# STM32.net
KiCad netlist of a schematic drawn in Altium Designer
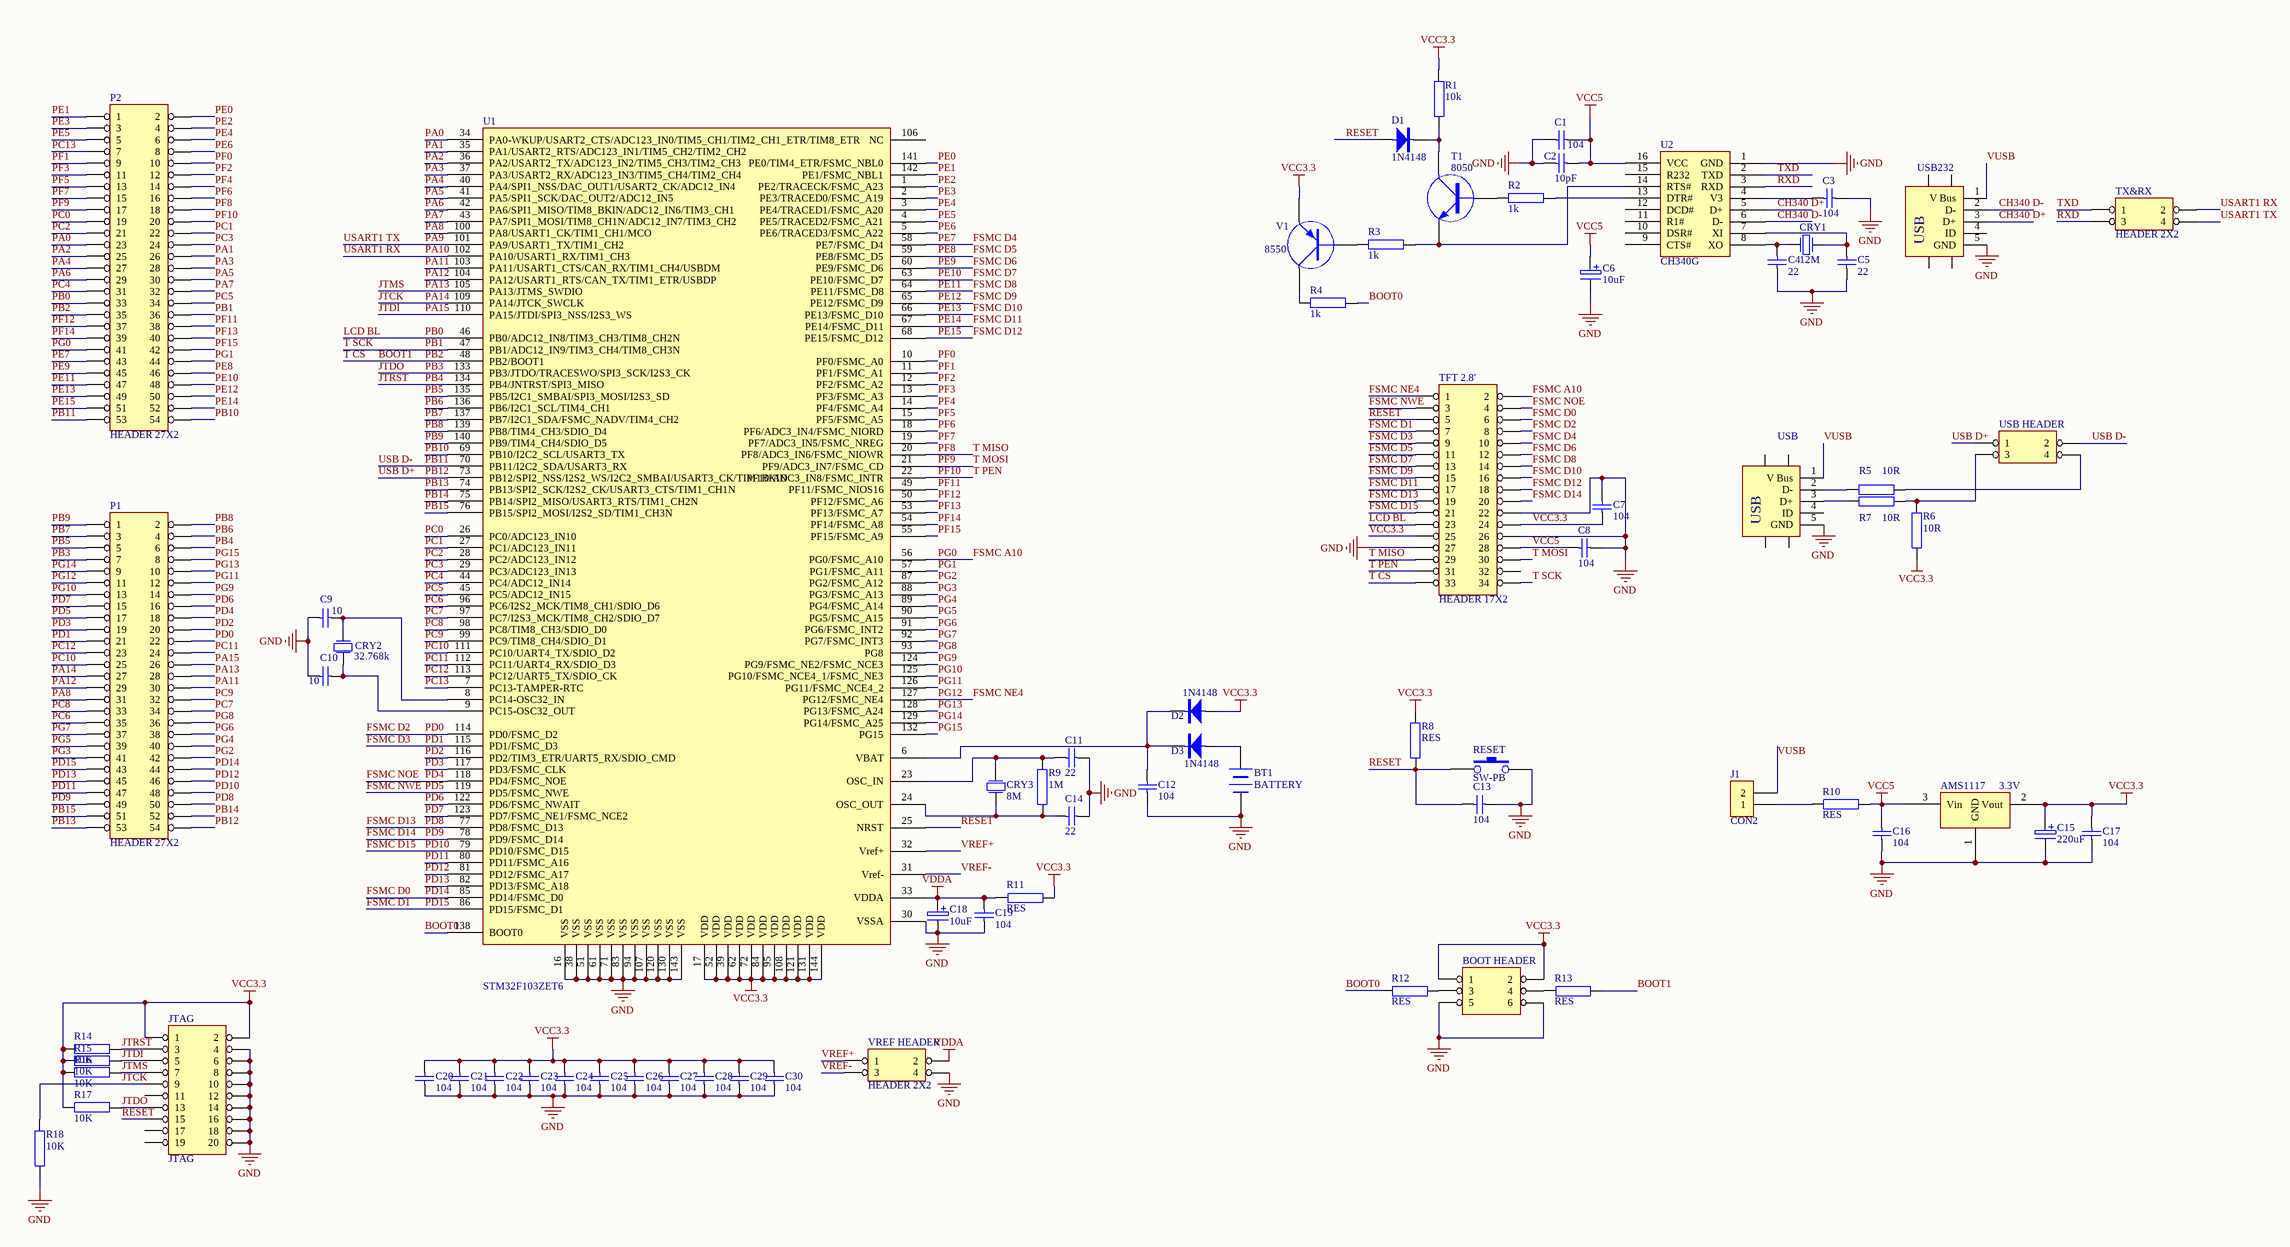
[diagram p0: STM32最小系统.SchDoc]

(export (version "E")
  (design (tool "Eeschema 10.0.6"))
  (components
    (comp (ref "AMS1117") (value "3.3V") (footprint "SOT-223") (libsource (lib "刘杨_元件库") (part "LD1117")))
    (comp (ref "BOOT HEADER")
      (value "HEADER 3X2")
      (footprint "3X2DIP")
      (libsource (lib "接口") (part "HEADER 3X2"))
    )
    (comp (ref "BT1")
      (value "BATTERY")
      (footprint "POWER1")
      (description "Battery")
      (libsource (lib "Other其它") (part "BATTERY"))
    )
    (comp (ref "C1")
      (value "104")
      (footprint "C0805")
      (description "Capacitor")
      (fields (field (name "PUBLISHER") "Altium Limited"))
      (libsource (lib "Capacitance电容") (part "Cap"))
    )
    (comp (ref "C2")
      (value "10pF")
      (footprint "C0805")
      (description "Capacitor")
      (fields (field (name "PUBLISHER") "Altium Limited"))
      (libsource (lib "Capacitance电容") (part "Cap"))
    )
    (comp (ref "C3")
      (value "104")
      (footprint "C0805")
      (description "Capacitor")
      (fields (field (name "PUBLISHER") "Altium Limited"))
      (libsource (lib "Capacitance电容") (part "Cap"))
    )
    (comp (ref "C4")
      (value "22")
      (footprint "C0805")
      (description "Capacitor")
      (fields (field (name "PUBLISHER") "Altium Limited"))
      (libsource (lib "Capacitance电容") (part "Cap"))
    )
    (comp (ref "C5")
      (value "22")
      (footprint "C0805")
      (description "Capacitor")
      (fields (field (name "PUBLISHER") "Altium Limited"))
      (libsource (lib "Capacitance电容") (part "Cap"))
    )
    (comp (ref "C6") (value "10uF") (footprint "CAO1") (libsource (lib "C电容") (part "CAP3")))
    (comp (ref "C7")
      (value "104")
      (footprint "C0805")
      (description "Capacitor")
      (fields (field (name "PUBLISHER") "Altium Limited"))
      (libsource (lib "Capacitance电容") (part "Cap"))
    )
    (comp (ref "C8")
      (value "104")
      (footprint "C0805")
      (description "Capacitor")
      (fields (field (name "PUBLISHER") "Altium Limited"))
      (libsource (lib "Capacitance电容") (part "Cap"))
    )
    (comp (ref "C9")
      (value "10")
      (footprint "C0805")
      (description "Capacitor")
      (fields (field (name "PUBLISHER") "Altium Limited"))
      (libsource (lib "Capacitance电容") (part "Cap"))
    )
    (comp (ref "C10")
      (value "10")
      (footprint "C0805")
      (description "Capacitor")
      (fields (field (name "PUBLISHER") "Altium Limited"))
      (libsource (lib "Capacitance电容") (part "Cap"))
    )
    (comp (ref "C11")
      (value "22")
      (footprint "C0805")
      (description "Capacitor")
      (fields (field (name "PUBLISHER") "Altium Limited"))
      (libsource (lib "Capacitance电容") (part "Cap"))
    )
    (comp (ref "C12")
      (value "104")
      (footprint "C0805")
      (description "Capacitor")
      (fields (field (name "PUBLISHER") "Altium Limited"))
      (libsource (lib "Capacitance电容") (part "Cap"))
    )
    (comp (ref "C13")
      (value "104")
      (footprint "C0805")
      (description "Capacitor")
      (fields (field (name "PUBLISHER") "Altium Limited"))
      (libsource (lib "Capacitance电容") (part "Cap"))
    )
    (comp (ref "C14")
      (value "22")
      (footprint "C0805")
      (description "Capacitor")
      (fields (field (name "PUBLISHER") "Altium Limited"))
      (libsource (lib "Capacitance电容") (part "Cap"))
    )
    (comp (ref "C15") (value "220uF") (footprint "CAO1") (libsource (lib "C电容") (part "CAP3")))
    (comp (ref "C16")
      (value "104")
      (footprint "C0805")
      (description "Capacitor")
      (fields (field (name "PUBLISHER") "Altium Limited"))
      (libsource (lib "Capacitance电容") (part "Cap"))
    )
    (comp (ref "C17")
      (value "104")
      (footprint "C0805")
      (description "Capacitor")
      (fields (field (name "PUBLISHER") "Altium Limited"))
      (libsource (lib "Capacitance电容") (part "Cap"))
    )
    (comp (ref "C18") (value "10uF") (footprint "CAO1") (libsource (lib "C电容") (part "CAP3")))
    (comp (ref "C19")
      (value "104")
      (footprint "C0805")
      (description "Capacitor")
      (fields (field (name "PUBLISHER") "Altium Limited"))
      (libsource (lib "Capacitance电容") (part "Cap"))
    )
    (comp (ref "C20")
      (value "104")
      (footprint "C0805")
      (description "Capacitor")
      (fields (field (name "PUBLISHER") "Altium Limited"))
      (libsource (lib "Capacitance电容") (part "Cap"))
    )
    (comp (ref "C21")
      (value "104")
      (footprint "C0805")
      (description "Capacitor")
      (fields (field (name "PUBLISHER") "Altium Limited"))
      (libsource (lib "Capacitance电容") (part "Cap"))
    )
    (comp (ref "C22")
      (value "104")
      (footprint "C0805")
      (description "Capacitor")
      (fields (field (name "PUBLISHER") "Altium Limited"))
      (libsource (lib "Capacitance电容") (part "Cap"))
    )
    (comp (ref "C23")
      (value "104")
      (footprint "C0805")
      (description "Capacitor")
      (fields (field (name "PUBLISHER") "Altium Limited"))
      (libsource (lib "Capacitance电容") (part "Cap"))
    )
    (comp (ref "C24")
      (value "104")
      (footprint "C0805")
      (description "Capacitor")
      (fields (field (name "PUBLISHER") "Altium Limited"))
      (libsource (lib "Capacitance电容") (part "Cap"))
    )
    (comp (ref "C25")
      (value "104")
      (footprint "C0805")
      (description "Capacitor")
      (fields (field (name "PUBLISHER") "Altium Limited"))
      (libsource (lib "Capacitance电容") (part "Cap"))
    )
    (comp (ref "C26")
      (value "104")
      (footprint "C0805")
      (description "Capacitor")
      (fields (field (name "PUBLISHER") "Altium Limited"))
      (libsource (lib "Capacitance电容") (part "Cap"))
    )
    (comp (ref "C27")
      (value "104")
      (footprint "C0805")
      (description "Capacitor")
      (fields (field (name "PUBLISHER") "Altium Limited"))
      (libsource (lib "Capacitance电容") (part "Cap"))
    )
    (comp (ref "C28")
      (value "104")
      (footprint "C0805")
      (description "Capacitor")
      (fields (field (name "PUBLISHER") "Altium Limited"))
      (libsource (lib "Capacitance电容") (part "Cap"))
    )
    (comp (ref "C29")
      (value "104")
      (footprint "C0805")
      (description "Capacitor")
      (fields (field (name "PUBLISHER") "Altium Limited"))
      (libsource (lib "Capacitance电容") (part "Cap"))
    )
    (comp (ref "C30")
      (value "104")
      (footprint "C0805")
      (description "Capacitor")
      (fields (field (name "PUBLISHER") "Altium Limited"))
      (libsource (lib "Capacitance电容") (part "Cap"))
    )
    (comp (ref "CRY1")
      (value "12M")
      (footprint "JZ1")
      (description "6.0000 8.000  11.0592  12.0000 24.000")
      (libsource (lib "J晶振") (part "CRY1"))
    )
    (comp (ref "CRY2")
      (value "32.768k")
      (footprint "JZ_O1")
      (description "6.0000 8.000  11.0592  12.0000 24.000")
      (libsource (lib "J晶振") (part "CRY1"))
    )
    (comp (ref "CRY3")
      (value "8M")
      (footprint "JZ1")
      (description "6.0000 8.000  11.0592  12.0000 24.000")
      (libsource (lib "J晶振") (part "CRY1"))
    )
    (comp (ref "D1") (value "1N4148") (footprint "DIODE0.4") (libsource (lib "") (part "DIODE_1")))
    (comp (ref "D2") (value "1N4148") (footprint "DIODE0.4") (libsource (lib "Diode二极管") (part "DIODE")))
    (comp (ref "D3") (value "1N4148") (footprint "DIODE0.4") (libsource (lib "Diode二极管") (part "DIODE")))
    (comp (ref "J1")
      (value "CON2")
      (footprint "sip-2")
      (description "Connector")
      (libsource (lib "接口") (part "CON2"))
    )
    (comp (ref "JTAG") (value "JTAG") (footprint "10x2DIP") (libsource (lib "接口") (part "HEADER 10X2")))
    (comp (ref "P1")
      (value "HEADER 27X2")
      (footprint "27X2DIP")
      (libsource (lib "Plugs插头") (part "HEADER 27X2"))
    )
    (comp (ref "P2")
      (value "HEADER 27X2")
      (footprint "27X2DIP")
      (libsource (lib "Plugs插头") (part "HEADER 27X2"))
    )
    (comp (ref "R1") (value "10k") (footprint "R0805") (libsource (lib "R电阻") (part "RES")))
    (comp (ref "R2") (value "1k") (footprint "R0805") (libsource (lib "R电阻") (part "RES")))
    (comp (ref "R3") (value "1k") (footprint "R0805") (libsource (lib "R电阻") (part "RES")))
    (comp (ref "R4") (value "1k") (footprint "R0805") (libsource (lib "R电阻") (part "RES")))
    (comp (ref "R5") (value "10R") (footprint "R0805") (libsource (lib "R电阻") (part "RES")))
    (comp (ref "R6") (value "10R") (footprint "R0805") (libsource (lib "R电阻") (part "RES")))
    (comp (ref "R7") (value "10R") (footprint "R0805") (libsource (lib "R电阻") (part "RES")))
    (comp (ref "R8") (value "RES") (footprint "R0805") (libsource (lib "R电阻") (part "RES")))
    (comp (ref "R9") (value "1M") (footprint "R0805") (libsource (lib "R电阻") (part "RES")))
    (comp (ref "R10") (value "RES") (footprint "R0805") (libsource (lib "R电阻") (part "RES")))
    (comp (ref "R11") (value "RES") (footprint "R0805") (libsource (lib "R电阻") (part "RES")))
    (comp (ref "R12") (value "RES") (footprint "R0805") (libsource (lib "R电阻") (part "RES")))
    (comp (ref "R13") (value "RES") (footprint "R0805") (libsource (lib "R电阻") (part "RES")))
    (comp (ref "R14") (value "10K") (footprint "R0805") (libsource (lib "R电阻") (part "RES")))
    (comp (ref "R15") (value "10K") (footprint "R0805") (libsource (lib "R电阻") (part "RES")))
    (comp (ref "R16") (value "10K") (footprint "R0805") (libsource (lib "R电阻") (part "RES")))
    (comp (ref "R17") (value "10K") (footprint "R0805") (libsource (lib "R电阻") (part "RES")))
    (comp (ref "R18") (value "10K") (footprint "R0805") (libsource (lib "R电阻") (part "RES")))
    (comp (ref "RESET") (value "SW-PB") (footprint "按键 15mm*15mm") (libsource (lib "SW开关") (part "SW-PB")))
    (comp (ref "T1") (value "8050") (footprint "TO-92") (libsource (lib "V三极管") (part "8050")))
    (comp (ref "TFT 2.8'")
      (value "HEADER 17X2")
      (footprint "17X2DIP")
      (libsource (lib "Plugs插头") (part "HEADER 17X2"))
    )
    (comp (ref "TX&RX") (value "HEADER 2X2") (footprint "2X2DIP") (libsource (lib "接口") (part "HEADER 2X2")))
    (comp (ref "U1")
      (value "STM32F103ZET6")
      (footprint "LQFN144")
      (libsource (lib "STM32") (part "STM32F103ZET6"))
    )
    (comp (ref "U2") (value "CH340G") (footprint "SOP16") (libsource (lib "ORDER其它") (part "CH340G")))
    (comp (ref "USB") (value "~") (footprint "USB_mini_B") (libsource (lib "Plugs插头") (part "USB_mini_B")))
    (comp (ref "USB HEADER") (value "~") (footprint "2X2DIP") (libsource (lib "接口") (part "HEADER 2X2")))
    (comp (ref "USB232") (value "~") (footprint "USB_mini_B") (libsource (lib "Plugs插头") (part "USB_mini_B")))
    (comp (ref "V1") (value "8550") (footprint "TO-92") (libsource (lib "V三极管") (part "8550")))
    (comp (ref "VREF HEADER")
      (value "HEADER 2X2")
      (footprint "2X2DIP")
      (libsource (lib "接口") (part "HEADER 2X2"))
    )
  )
  (nets
    (net (code "1") (name "/BOOT0") (class "Default")
      (node (ref "R12") (pin "1") (pinfunction "1_1") (pintype "passive"))
      (node (ref "R4") (pin "1") (pinfunction "1_1") (pintype "passive"))
      (node (ref "U1") (pin "138") (pinfunction "BOOT0_138") (pintype "passive"))
    )
    (net (code "2") (name "/BOOT1") (class "Default")
      (node (ref "P2") (pin "35") (pinfunction "35_35") (pintype "passive"))
      (node (ref "R13") (pin "2") (pinfunction "2_2") (pintype "passive"))
      (node (ref "TFT 2.8'") (pin "33") (pinfunction "33_33") (pintype "passive"))
      (node (ref "U1") (pin "48") (pinfunction "PB2/BOOT1_48") (pintype "passive"))
    )
    (net (code "3") (name "/CH340 D+") (class "Default")
      (node (ref "U2") (pin "5") (pinfunction "D+_5") (pintype "passive"))
      (node (ref "USB232") (pin "3") (pinfunction "D+_3") (pintype "passive"))
    )
    (net (code "4") (name "/CH340 D-") (class "Default")
      (node (ref "U2") (pin "6") (pinfunction "D-_6") (pintype "passive"))
      (node (ref "USB232") (pin "2") (pinfunction "D-_2") (pintype "passive"))
    )
    (net (code "5") (name "/FSMC A10") (class "Default")
      (node (ref "P2") (pin "41") (pinfunction "41_41") (pintype "passive"))
      (node (ref "TFT 2.8'") (pin "2") (pinfunction "2_2") (pintype "passive"))
      (node (ref "U1") (pin "56") (pinfunction "PG0/FSMC_A10_56") (pintype "passive"))
    )
    (net (code "6") (name "/FSMC D0") (class "Default")
      (node (ref "P1") (pin "44") (pinfunction "44_44") (pintype "passive"))
      (node (ref "TFT 2.8'") (pin "6") (pinfunction "6_6") (pintype "passive"))
      (node (ref "U1") (pin "85") (pinfunction "PD14/FSMC_D0_85") (pintype "passive"))
    )
    (net (code "7") (name "/FSMC D1") (class "Default")
      (node (ref "P1") (pin "43") (pinfunction "43_43") (pintype "passive"))
      (node (ref "TFT 2.8'") (pin "7") (pinfunction "7_7") (pintype "passive"))
      (node (ref "U1") (pin "86") (pinfunction "PD15/FSMC_D1_86") (pintype "passive"))
    )
    (net (code "8") (name "/FSMC D2") (class "Default")
      (node (ref "P1") (pin "22") (pinfunction "22_22") (pintype "passive"))
      (node (ref "TFT 2.8'") (pin "8") (pinfunction "8_8") (pintype "passive"))
      (node (ref "U1") (pin "114") (pinfunction "PD0/FSMC_D2_114") (pintype "passive"))
    )
    (net (code "9") (name "/FSMC D3") (class "Default")
      (node (ref "P1") (pin "21") (pinfunction "21_21") (pintype "passive"))
      (node (ref "TFT 2.8'") (pin "9") (pinfunction "9_9") (pintype "passive"))
      (node (ref "U1") (pin "115") (pinfunction "PD1/FSMC_D3_115") (pintype "passive"))
    )
    (net (code "10") (name "/FSMC D4") (class "Default")
      (node (ref "P2") (pin "43") (pinfunction "43_43") (pintype "passive"))
      (node (ref "TFT 2.8'") (pin "10") (pinfunction "10_10") (pintype "passive"))
      (node (ref "U1") (pin "58") (pinfunction "PE7/FSMC_D4_58") (pintype "passive"))
    )
    (net (code "11") (name "/FSMC D5") (class "Default")
      (node (ref "P2") (pin "46") (pinfunction "46_46") (pintype "passive"))
      (node (ref "TFT 2.8'") (pin "11") (pinfunction "11_11") (pintype "passive"))
      (node (ref "U1") (pin "59") (pinfunction "PE8/FSMC_D5_59") (pintype "passive"))
    )
    (net (code "12") (name "/FSMC D6") (class "Default")
      (node (ref "P2") (pin "45") (pinfunction "45_45") (pintype "passive"))
      (node (ref "TFT 2.8'") (pin "12") (pinfunction "12_12") (pintype "passive"))
      (node (ref "U1") (pin "60") (pinfunction "PE9/FSMC_D6_60") (pintype "passive"))
    )
    (net (code "13") (name "/FSMC D7") (class "Default")
      (node (ref "P2") (pin "48") (pinfunction "48_48") (pintype "passive"))
      (node (ref "TFT 2.8'") (pin "13") (pinfunction "13_13") (pintype "passive"))
      (node (ref "U1") (pin "63") (pinfunction "PE10/FSMC_D7_63") (pintype "passive"))
    )
    (net (code "14") (name "/FSMC D8") (class "Default")
      (node (ref "P2") (pin "47") (pinfunction "47_47") (pintype "passive"))
      (node (ref "TFT 2.8'") (pin "14") (pinfunction "14_14") (pintype "passive"))
      (node (ref "U1") (pin "64") (pinfunction "PE11/FSMC_D8_64") (pintype "passive"))
    )
    (net (code "15") (name "/FSMC D9") (class "Default")
      (node (ref "P2") (pin "50") (pinfunction "50_50") (pintype "passive"))
      (node (ref "TFT 2.8'") (pin "15") (pinfunction "15_15") (pintype "passive"))
      (node (ref "U1") (pin "65") (pinfunction "PE12/FSMC_D9_65") (pintype "passive"))
    )
    (net (code "16") (name "/FSMC D10") (class "Default")
      (node (ref "P2") (pin "49") (pinfunction "49_49") (pintype "passive"))
      (node (ref "TFT 2.8'") (pin "16") (pinfunction "16_16") (pintype "passive"))
      (node (ref "U1") (pin "66") (pinfunction "PE13/FSMC_D10_66") (pintype "passive"))
    )
    (net (code "17") (name "/FSMC D11") (class "Default")
      (node (ref "P2") (pin "52") (pinfunction "52_52") (pintype "passive"))
      (node (ref "TFT 2.8'") (pin "17") (pinfunction "17_17") (pintype "passive"))
      (node (ref "U1") (pin "67") (pinfunction "PE14/FSMC_D11_67") (pintype "passive"))
    )
    (net (code "18") (name "/FSMC D12") (class "Default")
      (node (ref "P2") (pin "51") (pinfunction "51_51") (pintype "passive"))
      (node (ref "TFT 2.8'") (pin "18") (pinfunction "18_18") (pintype "passive"))
      (node (ref "U1") (pin "68") (pinfunction "PE15/FSMC_D12_68") (pintype "passive"))
    )
    (net (code "19") (name "/FSMC D13") (class "Default")
      (node (ref "P1") (pin "50") (pinfunction "50_50") (pintype "passive"))
      (node (ref "TFT 2.8'") (pin "19") (pinfunction "19_19") (pintype "passive"))
      (node (ref "U1") (pin "77") (pinfunction "PD8/FSMC_D13_77") (pintype "passive"))
    )
    (net (code "20") (name "/FSMC D14") (class "Default")
      (node (ref "P1") (pin "49") (pinfunction "49_49") (pintype "passive"))
      (node (ref "TFT 2.8'") (pin "20") (pinfunction "20_20") (pintype "passive"))
      (node (ref "U1") (pin "78") (pinfunction "PD9/FSMC_D14_78") (pintype "passive"))
    )
    (net (code "21") (name "/FSMC D15") (class "Default")
      (node (ref "P1") (pin "48") (pinfunction "48_48") (pintype "passive"))
      (node (ref "TFT 2.8'") (pin "21") (pinfunction "21_21") (pintype "passive"))
      (node (ref "U1") (pin "79") (pinfunction "PD10/FSMC_D15_79") (pintype "passive"))
    )
    (net (code "22") (name "/FSMC NE4") (class "Default")
      (node (ref "P1") (pin "11") (pinfunction "11_11") (pintype "passive"))
      (node (ref "TFT 2.8'") (pin "1") (pinfunction "1_1") (pintype "passive"))
      (node (ref "U1") (pin "127") (pinfunction "PG12/FSMC_NE4_127") (pintype "passive"))
    )
    (net (code "23") (name "/FSMC NOE") (class "Default")
      (node (ref "P1") (pin "18") (pinfunction "18_18") (pintype "passive"))
      (node (ref "TFT 2.8'") (pin "4") (pinfunction "4_4") (pintype "passive"))
      (node (ref "U1") (pin "118") (pinfunction "PD4/FSMC_NOE_118") (pintype "passive"))
    )
    (net (code "24") (name "/FSMC NWE") (class "Default")
      (node (ref "P1") (pin "17") (pinfunction "17_17") (pintype "passive"))
      (node (ref "TFT 2.8'") (pin "3") (pinfunction "3_3") (pintype "passive"))
      (node (ref "U1") (pin "119") (pinfunction "PD5/FSMC_NWE_119") (pintype "passive"))
    )
    (net (code "25") (name "/JTCK") (class "Default")
      (node (ref "JTAG") (pin "9") (pinfunction "9_9") (pintype "passive"))
      (node (ref "P1") (pin "27") (pinfunction "27_27") (pintype "passive"))
      (node (ref "R18") (pin "2") (pinfunction "2_2") (pintype "passive"))
      (node (ref "U1") (pin "109") (pinfunction "PA14/JTCK_SWCLK_109") (pintype "passive"))
    )
    (net (code "26") (name "/JTDI") (class "Default")
      (node (ref "JTAG") (pin "5") (pinfunction "5_5") (pintype "passive"))
      (node (ref "P1") (pin "26") (pinfunction "26_26") (pintype "passive"))
      (node (ref "R15") (pin "1") (pinfunction "1_1") (pintype "passive"))
      (node (ref "U1") (pin "110") (pinfunction "PA15/JTDI/SPI3_NSS/I2S3_WS_110") (pintype "passive"))
    )
    (net (code "27") (name "/JTDO") (class "Default")
      (node (ref "JTAG") (pin "13") (pinfunction "13_13") (pintype "passive"))
      (node (ref "P1") (pin "7") (pinfunction "7_7") (pintype "passive"))
      (node (ref "R17") (pin "1") (pinfunction "1_1") (pintype "passive"))
      (node (ref "U1") (pin "133") (pinfunction "PB3/JTDO/TRACESWO/SPI3_SCK/I2S3_CK_133") (pintype "passive"))
    )
    (net (code "28") (name "/JTMS") (class "Default")
      (node (ref "JTAG") (pin "7") (pinfunction "7_7") (pintype "passive"))
      (node (ref "P1") (pin "28") (pinfunction "28_28") (pintype "passive"))
      (node (ref "R16") (pin "1") (pinfunction "1_1") (pintype "passive"))
      (node (ref "U1") (pin "105") (pinfunction "PA13/JTMS_SWDIO_105") (pintype "passive"))
    )
    (net (code "29") (name "/JTRST") (class "Default")
      (node (ref "JTAG") (pin "3") (pinfunction "3_3") (pintype "passive"))
      (node (ref "P1") (pin "6") (pinfunction "6_6") (pintype "passive"))
      (node (ref "R14") (pin "1") (pinfunction "1_1") (pintype "passive"))
      (node (ref "U1") (pin "134") (pinfunction "PB4/JNTRST/SPI3_MISO_134") (pintype "passive"))
    )
    (net (code "30") (name "/LCD BL") (class "Default")
      (node (ref "P2") (pin "33") (pinfunction "33_33") (pintype "passive"))
      (node (ref "TFT 2.8'") (pin "23") (pinfunction "23_23") (pintype "passive"))
      (node (ref "U1") (pin "46") (pinfunction "PB0/ADC12_IN8/TIM3_CH3/TIM8_CH2N_46") (pintype "passive"))
    )
    (net (code "31") (name "/PA0") (class "Default")
      (node (ref "P2") (pin "23") (pinfunction "23_23") (pintype "passive"))
      (node (ref "U1") (pin "34") (pinfunction "PA0-WKUP/USART2_CTS/ADC123_IN0/TIM5_CH1/TIM2_CH1_ETR/TIM8_ETR_34") (pintype "passive"))
    )
    (net (code "32") (name "/PA1") (class "Default")
      (node (ref "P2") (pin "26") (pinfunction "26_26") (pintype "passive"))
      (node (ref "U1") (pin "35") (pinfunction "PA1/USART2_RTS/ADC123_IN1/TIM5_CH2/TIM2_CH2_35") (pintype "passive"))
    )
    (net (code "33") (name "/PA2") (class "Default")
      (node (ref "P2") (pin "25") (pinfunction "25_25") (pintype "passive"))
      (node (ref "U1") (pin "36") (pinfunction "PA2/USART2_TX/ADC123_IN2/TIM5_CH3/TIM2_CH3_36") (pintype "passive"))
    )
    (net (code "34") (name "/PA3") (class "Default")
      (node (ref "P2") (pin "28") (pinfunction "28_28") (pintype "passive"))
      (node (ref "U1") (pin "37") (pinfunction "PA3/USART2_RX/ADC123_IN3/TIM5_CH4/TIM2_CH4_37") (pintype "passive"))
    )
    (net (code "35") (name "/PA4") (class "Default")
      (node (ref "P2") (pin "27") (pinfunction "27_27") (pintype "passive"))
      (node (ref "U1") (pin "40") (pinfunction "PA4/SPI1_NSS/DAC_OUT1/USART2_CK/ADC12_IN4_40") (pintype "passive"))
    )
    (net (code "36") (name "/PA5") (class "Default")
      (node (ref "P2") (pin "30") (pinfunction "30_30") (pintype "passive"))
      (node (ref "U1") (pin "41") (pinfunction "PA5/SPI1_SCK/DAC_OUT2/ADC12_IN5_41") (pintype "passive"))
    )
    (net (code "37") (name "/PA6") (class "Default")
      (node (ref "P2") (pin "29") (pinfunction "29_29") (pintype "passive"))
      (node (ref "U1") (pin "42") (pinfunction "PA6/SPI1_MISO/TIM8_BKIN/ADC12_IN6/TIM3_CH1_42") (pintype "passive"))
    )
    (net (code "38") (name "/PA7") (class "Default")
      (node (ref "P2") (pin "32") (pinfunction "32_32") (pintype "passive"))
      (node (ref "U1") (pin "43") (pinfunction "PA7/SPI1_MOSI/TIM8_CH1N/ADC12_IN7/TIM3_CH2_43") (pintype "passive"))
    )
    (net (code "39") (name "/PA8") (class "Default")
      (node (ref "P1") (pin "31") (pinfunction "31_31") (pintype "passive"))
      (node (ref "U1") (pin "100") (pinfunction "PA8/USART1_CK/TIM1_CH1/MCO_100") (pintype "passive"))
    )
    (net (code "40") (name "/PA9") (class "Default")
      (node (ref "TX&RX") (pin "4") (pinfunction "4_4") (pintype "passive"))
      (node (ref "U1") (pin "101") (pinfunction "PA9/USART1_TX/TIM1_CH2_101") (pintype "passive"))
    )
    (net (code "41") (name "/PA10") (class "Default")
      (node (ref "TX&RX") (pin "2") (pinfunction "2_2") (pintype "passive"))
      (node (ref "U1") (pin "102") (pinfunction "PA10/USART1_RX/TIM1_CH3_102") (pintype "passive"))
    )
    (net (code "42") (name "/PA11") (class "Default")
      (node (ref "P1") (pin "30") (pinfunction "30_30") (pintype "passive"))
      (node (ref "U1") (pin "103") (pinfunction "PA11/USART1_CTS/CAN_RX/TIM1_CH4/USBDM_103") (pintype "passive"))
    )
    (net (code "43") (name "/PA12") (class "Default")
      (node (ref "P1") (pin "29") (pinfunction "29_29") (pintype "passive"))
      (node (ref "U1") (pin "104") (pinfunction "PA12/USART1_RTS/CAN_TX/TIM1_ETR/USBDP_104") (pintype "passive"))
    )
    (net (code "44") (name "/PB1") (class "Default")
      (node (ref "P2") (pin "36") (pinfunction "36_36") (pintype "passive"))
      (node (ref "TFT 2.8'") (pin "34") (pinfunction "34_34") (pintype "passive"))
      (node (ref "U1") (pin "47") (pinfunction "PB1/ADC12_IN9/TIM3_CH4/TIM8_CH3N_47") (pintype "passive"))
    )
    (net (code "45") (name "/PB5") (class "Default")
      (node (ref "P1") (pin "5") (pinfunction "5_5") (pintype "passive"))
      (node (ref "U1") (pin "135") (pinfunction "PB5/I2C1_SMBAI/SPI3_MOSI/I2S3_SD_135") (pintype "passive"))
    )
    (net (code "46") (name "/PB6") (class "Default")
      (node (ref "P1") (pin "4") (pinfunction "4_4") (pintype "passive"))
      (node (ref "U1") (pin "136") (pinfunction "PB6/I2C1_SCL/TIM4_CH1_136") (pintype "passive"))
    )
    (net (code "47") (name "/PB7") (class "Default")
      (node (ref "P1") (pin "3") (pinfunction "3_3") (pintype "passive"))
      (node (ref "U1") (pin "137") (pinfunction "PB7/I2C1_SDA/FSMC_NADV/TIM4_CH2_137") (pintype "passive"))
    )
    (net (code "48") (name "/PB8") (class "Default")
      (node (ref "P1") (pin "2") (pinfunction "2_2") (pintype "passive"))
      (node (ref "U1") (pin "139") (pinfunction "PB8/TIM4_CH3/SDIO_D4_139") (pintype "passive"))
    )
    (net (code "49") (name "/PB9") (class "Default")
      (node (ref "P1") (pin "1") (pinfunction "1_1") (pintype "passive"))
      (node (ref "U1") (pin "140") (pinfunction "PB9/TIM4_CH4/SDIO_D5_140") (pintype "passive"))
    )
    (net (code "50") (name "/PB10") (class "Default")
      (node (ref "P2") (pin "54") (pinfunction "54_54") (pintype "passive"))
      (node (ref "U1") (pin "69") (pinfunction "PB10/I2C2_SCL/USART3_TX_69") (pintype "passive"))
    )
    (net (code "51") (name "/PB11") (class "Default")
      (node (ref "P2") (pin "53") (pinfunction "53_53") (pintype "passive"))
      (node (ref "U1") (pin "70") (pinfunction "PB11/I2C2_SDA/USART3_RX_70") (pintype "passive"))
      (node (ref "USB HEADER") (pin "2") (pinfunction "2_2") (pintype "passive"))
    )
    (net (code "52") (name "/PB12") (class "Default")
      (node (ref "P1") (pin "54") (pinfunction "54_54") (pintype "passive"))
      (node (ref "U1") (pin "73") (pinfunction "PB12/SPI2_NSS/I2S2_WS/I2C2_SMBAI/USART3_CK/TIM1BKIN_73") (pintype "passive"))
      (node (ref "USB HEADER") (pin "1") (pinfunction "1_1") (pintype "passive"))
    )
    (net (code "53") (name "/PB13") (class "Default")
      (node (ref "P1") (pin "53") (pinfunction "53_53") (pintype "passive"))
      (node (ref "U1") (pin "74") (pinfunction "PB13/SPI2_SCK/I2S2_CK/USART3_CTS/TIM1_CH1N_74") (pintype "passive"))
    )
    (net (code "54") (name "/PB14") (class "Default")
      (node (ref "P1") (pin "52") (pinfunction "52_52") (pintype "passive"))
      (node (ref "U1") (pin "75") (pinfunction "PB14/SPI2_MISO/USART3_RTS/TIM1_CH2N_75") (pintype "passive"))
    )
    (net (code "55") (name "/PB15") (class "Default")
      (node (ref "P1") (pin "51") (pinfunction "51_51") (pintype "passive"))
      (node (ref "U1") (pin "76") (pinfunction "PB15/SPI2_MOSI/I2S2_SD/TIM1_CH3N_76") (pintype "passive"))
    )
    (net (code "56") (name "/PC0") (class "Default")
      (node (ref "P2") (pin "19") (pinfunction "19_19") (pintype "passive"))
      (node (ref "U1") (pin "26") (pinfunction "PC0/ADC123_IN10_26") (pintype "passive"))
    )
    (net (code "57") (name "/PC1") (class "Default")
      (node (ref "P2") (pin "22") (pinfunction "22_22") (pintype "passive"))
      (node (ref "U1") (pin "27") (pinfunction "PC1/ADC123_IN11_27") (pintype "passive"))
    )
    (net (code "58") (name "/PC2") (class "Default")
      (node (ref "P2") (pin "21") (pinfunction "21_21") (pintype "passive"))
      (node (ref "U1") (pin "28") (pinfunction "PC2/ADC123_IN12_28") (pintype "passive"))
    )
    (net (code "59") (name "/PC3") (class "Default")
      (node (ref "P2") (pin "24") (pinfunction "24_24") (pintype "passive"))
      (node (ref "U1") (pin "29") (pinfunction "PC3/ADC123_IN13_29") (pintype "passive"))
    )
    (net (code "60") (name "/PC4") (class "Default")
      (node (ref "P2") (pin "31") (pinfunction "31_31") (pintype "passive"))
      (node (ref "U1") (pin "44") (pinfunction "PC4/ADC12_IN14_44") (pintype "passive"))
    )
    (net (code "61") (name "/PC5") (class "Default")
      (node (ref "P2") (pin "34") (pinfunction "34_34") (pintype "passive"))
      (node (ref "U1") (pin "45") (pinfunction "PC5/ADC12_IN15_45") (pintype "passive"))
    )
    (net (code "62") (name "/PC6") (class "Default")
      (node (ref "P1") (pin "35") (pinfunction "35_35") (pintype "passive"))
      (node (ref "U1") (pin "96") (pinfunction "PC6/I2S2_MCK/TIM8_CH1/SDIO_D6_96") (pintype "passive"))
    )
    (net (code "63") (name "/PC7") (class "Default")
      (node (ref "P1") (pin "34") (pinfunction "34_34") (pintype "passive"))
      (node (ref "U1") (pin "97") (pinfunction "PC7/I2S3_MCK/TIM8_CH2/SDIO_D7_97") (pintype "passive"))
    )
    (net (code "64") (name "/PC8") (class "Default")
      (node (ref "P1") (pin "33") (pinfunction "33_33") (pintype "passive"))
      (node (ref "U1") (pin "98") (pinfunction "PC8/TIM8_CH3/SDIO_D0_98") (pintype "passive"))
    )
    (net (code "65") (name "/PC9") (class "Default")
      (node (ref "P1") (pin "32") (pinfunction "32_32") (pintype "passive"))
      (node (ref "U1") (pin "99") (pinfunction "PC9/TIM8_CH4/SDIO_D1_99") (pintype "passive"))
    )
    (net (code "66") (name "/PC10") (class "Default")
      (node (ref "P1") (pin "25") (pinfunction "25_25") (pintype "passive"))
      (node (ref "U1") (pin "111") (pinfunction "PC10/UART4_TX/SDIO_D2_111") (pintype "passive"))
    )
    (net (code "67") (name "/PC11") (class "Default")
      (node (ref "P1") (pin "24") (pinfunction "24_24") (pintype "passive"))
      (node (ref "U1") (pin "112") (pinfunction "PC11/UART4_RX/SDIO_D3_112") (pintype "passive"))
    )
    (net (code "68") (name "/PC12") (class "Default")
      (node (ref "P1") (pin "23") (pinfunction "23_23") (pintype "passive"))
      (node (ref "U1") (pin "113") (pinfunction "PC12/UART5_TX/SDIO_CK_113") (pintype "passive"))
    )
    (net (code "69") (name "/PC13") (class "Default")
      (node (ref "P2") (pin "7") (pinfunction "7_7") (pintype "passive"))
      (node (ref "U1") (pin "7") (pinfunction "PC13-TAMPER-RTC_7") (pintype "passive"))
    )
    (net (code "70") (name "/PD2") (class "Default")
      (node (ref "P1") (pin "20") (pinfunction "20_20") (pintype "passive"))
      (node (ref "U1") (pin "116") (pinfunction "PD2/TIM3_ETR/UART5_RX/SDIO_CMD_116") (pintype "passive"))
    )
    (net (code "71") (name "/PD3") (class "Default")
      (node (ref "P1") (pin "19") (pinfunction "19_19") (pintype "passive"))
      (node (ref "U1") (pin "117") (pinfunction "PD3/FSMC_CLK_117") (pintype "passive"))
    )
    (net (code "72") (name "/PD6") (class "Default")
      (node (ref "P1") (pin "16") (pinfunction "16_16") (pintype "passive"))
      (node (ref "U1") (pin "122") (pinfunction "PD6/FSMC_NWAIT_122") (pintype "passive"))
    )
    (net (code "73") (name "/PD7") (class "Default")
      (node (ref "P1") (pin "15") (pinfunction "15_15") (pintype "passive"))
      (node (ref "U1") (pin "123") (pinfunction "PD7/FSMC_NE1/FSMC_NCE2_123") (pintype "passive"))
    )
    (net (code "74") (name "/PD11") (class "Default")
      (node (ref "P1") (pin "47") (pinfunction "47_47") (pintype "passive"))
      (node (ref "U1") (pin "80") (pinfunction "PD11/FSMC_A16_80") (pintype "passive"))
    )
    (net (code "75") (name "/PD12") (class "Default")
      (node (ref "P1") (pin "46") (pinfunction "46_46") (pintype "passive"))
      (node (ref "U1") (pin "81") (pinfunction "PD12/FSMC_A17_81") (pintype "passive"))
    )
    (net (code "76") (name "/PD13") (class "Default")
      (node (ref "P1") (pin "45") (pinfunction "45_45") (pintype "passive"))
      (node (ref "U1") (pin "82") (pinfunction "PD13/FSMC_A18_82") (pintype "passive"))
    )
    (net (code "77") (name "/PE0") (class "Default")
      (node (ref "P2") (pin "2") (pinfunction "2_2") (pintype "passive"))
      (node (ref "U1") (pin "141") (pinfunction "PE0/TIM4_ETR/FSMC_NBL0_141") (pintype "passive"))
    )
    (net (code "78") (name "/PE1") (class "Default")
      (node (ref "P2") (pin "1") (pinfunction "1_1") (pintype "passive"))
      (node (ref "U1") (pin "142") (pinfunction "PE1/FSMC_NBL1_142") (pintype "passive"))
    )
    (net (code "79") (name "/PE2") (class "Default")
      (node (ref "P2") (pin "4") (pinfunction "4_4") (pintype "passive"))
      (node (ref "U1") (pin "1") (pinfunction "PE2/TRACECK/FSMC_A23_1") (pintype "passive"))
    )
    (net (code "80") (name "/PE3") (class "Default")
      (node (ref "P2") (pin "3") (pinfunction "3_3") (pintype "passive"))
      (node (ref "U1") (pin "2") (pinfunction "PE3/TRACED0/FSMC_A19_2") (pintype "passive"))
    )
    (net (code "81") (name "/PE4") (class "Default")
      (node (ref "P2") (pin "6") (pinfunction "6_6") (pintype "passive"))
      (node (ref "U1") (pin "3") (pinfunction "PE4/TRACED1/FSMC_A20_3") (pintype "passive"))
    )
    (net (code "82") (name "/PE5") (class "Default")
      (node (ref "P2") (pin "5") (pinfunction "5_5") (pintype "passive"))
      (node (ref "U1") (pin "4") (pinfunction "PE5/TRACED2/FSMC_A21_4") (pintype "passive"))
    )
    (net (code "83") (name "/PE6") (class "Default")
      (node (ref "P2") (pin "8") (pinfunction "8_8") (pintype "passive"))
      (node (ref "U1") (pin "5") (pinfunction "PE6/TRACED3/FSMC_A22_5") (pintype "passive"))
    )
    (net (code "84") (name "/PF0") (class "Default")
      (node (ref "P2") (pin "10") (pinfunction "10_10") (pintype "passive"))
      (node (ref "U1") (pin "10") (pinfunction "PF0/FSMC_A0_10") (pintype "passive"))
    )
    (net (code "85") (name "/PF1") (class "Default")
      (node (ref "P2") (pin "9") (pinfunction "9_9") (pintype "passive"))
      (node (ref "U1") (pin "11") (pinfunction "PF1/FSMC_A1_11") (pintype "passive"))
    )
    (net (code "86") (name "/PF2") (class "Default")
      (node (ref "P2") (pin "12") (pinfunction "12_12") (pintype "passive"))
      (node (ref "U1") (pin "12") (pinfunction "PF2/FSMC_A2_12") (pintype "passive"))
    )
    (net (code "87") (name "/PF3") (class "Default")
      (node (ref "P2") (pin "11") (pinfunction "11_11") (pintype "passive"))
      (node (ref "U1") (pin "13") (pinfunction "PF3/FSMC_A3_13") (pintype "passive"))
    )
    (net (code "88") (name "/PF4") (class "Default")
      (node (ref "P2") (pin "14") (pinfunction "14_14") (pintype "passive"))
      (node (ref "U1") (pin "14") (pinfunction "PF4/FSMC_A4_14") (pintype "passive"))
    )
    (net (code "89") (name "/PF5") (class "Default")
      (node (ref "P2") (pin "13") (pinfunction "13_13") (pintype "passive"))
      (node (ref "U1") (pin "15") (pinfunction "PF5/FSMC_A5_15") (pintype "passive"))
    )
    (net (code "90") (name "/PF6") (class "Default")
      (node (ref "P2") (pin "16") (pinfunction "16_16") (pintype "passive"))
      (node (ref "U1") (pin "18") (pinfunction "PF6/ADC3_IN4/FSMC_NIORD_18") (pintype "passive"))
    )
    (net (code "91") (name "/PF7") (class "Default")
      (node (ref "P2") (pin "15") (pinfunction "15_15") (pintype "passive"))
      (node (ref "U1") (pin "19") (pinfunction "PF7/ADC3_IN5/FSMC_NREG_19") (pintype "passive"))
    )
    (net (code "92") (name "/PF8") (class "Default")
      (node (ref "P2") (pin "18") (pinfunction "18_18") (pintype "passive"))
      (node (ref "TFT 2.8'") (pin "29") (pinfunction "29_29") (pintype "passive"))
      (node (ref "U1") (pin "20") (pinfunction "PF8/ADC3_IN6/FSMC_NIOWR_20") (pintype "passive"))
    )
    (net (code "93") (name "/PF9") (class "Default")
      (node (ref "P2") (pin "17") (pinfunction "17_17") (pintype "passive"))
      (node (ref "TFT 2.8'") (pin "30") (pinfunction "30_30") (pintype "passive"))
      (node (ref "U1") (pin "21") (pinfunction "PF9/ADC3_IN7/FSMC_CD_21") (pintype "passive"))
    )
    (net (code "94") (name "/PF10") (class "Default")
      (node (ref "P2") (pin "20") (pinfunction "20_20") (pintype "passive"))
      (node (ref "TFT 2.8'") (pin "31") (pinfunction "31_31") (pintype "passive"))
      (node (ref "U1") (pin "22") (pinfunction "PF10/ADC3_IN8/FSMC_INTR_22") (pintype "passive"))
    )
    (net (code "95") (name "/PF11") (class "Default")
      (node (ref "P2") (pin "38") (pinfunction "38_38") (pintype "passive"))
      (node (ref "U1") (pin "49") (pinfunction "PF11/FSMC_NIOS16_49") (pintype "passive"))
    )
    (net (code "96") (name "/PF12") (class "Default")
      (node (ref "P2") (pin "37") (pinfunction "37_37") (pintype "passive"))
      (node (ref "U1") (pin "50") (pinfunction "PF12/FSMC_A6_50") (pintype "passive"))
    )
    (net (code "97") (name "/PF13") (class "Default")
      (node (ref "P2") (pin "40") (pinfunction "40_40") (pintype "passive"))
      (node (ref "U1") (pin "53") (pinfunction "PF13/FSMC_A7_53") (pintype "passive"))
    )
    (net (code "98") (name "/PF14") (class "Default")
      (node (ref "P2") (pin "39") (pinfunction "39_39") (pintype "passive"))
      (node (ref "U1") (pin "54") (pinfunction "PF14/FSMC_A8_54") (pintype "passive"))
    )
    (net (code "99") (name "/PF15") (class "Default")
      (node (ref "P2") (pin "42") (pinfunction "42_42") (pintype "passive"))
      (node (ref "U1") (pin "55") (pinfunction "PF15/FSMC_A9_55") (pintype "passive"))
    )
    (net (code "100") (name "/PG1") (class "Default")
      (node (ref "P2") (pin "44") (pinfunction "44_44") (pintype "passive"))
      (node (ref "U1") (pin "57") (pinfunction "PG1/FSMC_A11_57") (pintype "passive"))
    )
    (net (code "101") (name "/PG2") (class "Default")
      (node (ref "P1") (pin "42") (pinfunction "42_42") (pintype "passive"))
      (node (ref "U1") (pin "87") (pinfunction "PG2/FSMC_A12_87") (pintype "passive"))
    )
    (net (code "102") (name "/PG3") (class "Default")
      (node (ref "P1") (pin "41") (pinfunction "41_41") (pintype "passive"))
      (node (ref "U1") (pin "88") (pinfunction "PG3/FSMC_A13_88") (pintype "passive"))
    )
    (net (code "103") (name "/PG4") (class "Default")
      (node (ref "P1") (pin "40") (pinfunction "40_40") (pintype "passive"))
      (node (ref "U1") (pin "89") (pinfunction "PG4/FSMC_A14_89") (pintype "passive"))
    )
    (net (code "104") (name "/PG5") (class "Default")
      (node (ref "P1") (pin "39") (pinfunction "39_39") (pintype "passive"))
      (node (ref "U1") (pin "90") (pinfunction "PG5/FSMC_A15_90") (pintype "passive"))
    )
    (net (code "105") (name "/PG6") (class "Default")
      (node (ref "P1") (pin "38") (pinfunction "38_38") (pintype "passive"))
      (node (ref "U1") (pin "91") (pinfunction "PG6/FSMC_INT2_91") (pintype "passive"))
    )
    (net (code "106") (name "/PG7") (class "Default")
      (node (ref "P1") (pin "37") (pinfunction "37_37") (pintype "passive"))
      (node (ref "U1") (pin "92") (pinfunction "PG7/FSMC_INT3_92") (pintype "passive"))
    )
    (net (code "107") (name "/PG8") (class "Default")
      (node (ref "P1") (pin "36") (pinfunction "36_36") (pintype "passive"))
      (node (ref "U1") (pin "93") (pinfunction "PG8_93") (pintype "passive"))
    )
    (net (code "108") (name "/PG9") (class "Default")
      (node (ref "P1") (pin "14") (pinfunction "14_14") (pintype "passive"))
      (node (ref "U1") (pin "124") (pinfunction "PG9/FSMC_NE2/FSMC_NCE3_124") (pintype "passive"))
    )
    (net (code "109") (name "/PG10") (class "Default")
      (node (ref "P1") (pin "13") (pinfunction "13_13") (pintype "passive"))
      (node (ref "U1") (pin "125") (pinfunction "PG10/FSMC_NCE4_1/FSMC_NE3_125") (pintype "passive"))
    )
    (net (code "110") (name "/PG11") (class "Default")
      (node (ref "P1") (pin "12") (pinfunction "12_12") (pintype "passive"))
      (node (ref "U1") (pin "126") (pinfunction "PG11/FSMC_NCE4_2_126") (pintype "passive"))
    )
    (net (code "111") (name "/PG13") (class "Default")
      (node (ref "P1") (pin "10") (pinfunction "10_10") (pintype "passive"))
      (node (ref "U1") (pin "128") (pinfunction "PG13/FSMC_A24_128") (pintype "passive"))
    )
    (net (code "112") (name "/PG14") (class "Default")
      (node (ref "P1") (pin "9") (pinfunction "9_9") (pintype "passive"))
      (node (ref "U1") (pin "129") (pinfunction "PG14/FSMC_A25_129") (pintype "passive"))
    )
    (net (code "113") (name "/PG15") (class "Default")
      (node (ref "P1") (pin "8") (pinfunction "8_8") (pintype "passive"))
      (node (ref "U1") (pin "132") (pinfunction "PG15_132") (pintype "passive"))
    )
    (net (code "114") (name "/RESET") (class "Default")
      (node (ref "C13") (pin "2") (pinfunction "2_2") (pintype "passive"))
      (node (ref "D1") (pin "1") (pinfunction "1_1") (pintype "passive"))
      (node (ref "JTAG") (pin "15") (pinfunction "15_15") (pintype "passive"))
      (node (ref "R8") (pin "1") (pinfunction "1_1") (pintype "passive"))
      (node (ref "RESET") (pin "1") (pinfunction "1_1") (pintype "passive"))
      (node (ref "TFT 2.8'") (pin "5") (pinfunction "5_5") (pintype "passive"))
      (node (ref "U1") (pin "25") (pinfunction "NRST_25") (pintype "passive"))
    )
    (net (code "115") (name "/RXD") (class "Default")
      (node (ref "TX&RX") (pin "3") (pinfunction "3_3") (pintype "passive"))
      (node (ref "U2") (pin "3") (pinfunction "RXD_3") (pintype "passive"))
    )
    (net (code "116") (name "/TXD") (class "Default")
      (node (ref "TX&RX") (pin "1") (pinfunction "1_1") (pintype "passive"))
      (node (ref "U2") (pin "2") (pinfunction "TXD_2") (pintype "passive"))
    )
    (net (code "117") (name "/VREF+") (class "Default")
      (node (ref "U1") (pin "32") (pinfunction "Vref+_32") (pintype "passive"))
      (node (ref "VREF HEADER") (pin "1") (pinfunction "1_1") (pintype "passive"))
    )
    (net (code "118") (name "/VREF-") (class "Default")
      (node (ref "U1") (pin "31") (pinfunction "Vref-_31") (pintype "passive"))
      (node (ref "VREF HEADER") (pin "3") (pinfunction "3_3") (pintype "passive"))
    )
    (net (code "119") (name "/VUSB") (class "Default")
      (node (ref "J1") (pin "2") (pinfunction "2_2") (pintype "passive"))
      (node (ref "USB") (pin "1") (pinfunction "V_Bus_1") (pintype "passive"))
      (node (ref "USB232") (pin "1") (pinfunction "V_Bus_1") (pintype "passive"))
    )
    (net (code "120") (name "GND") (class "Default")
      (node (ref "AMS1117") (pin "1") (pinfunction "GND_1") (pintype "passive"))
      (node (ref "BOOT HEADER") (pin "5") (pinfunction "5_5") (pintype "passive"))
      (node (ref "BOOT HEADER") (pin "6") (pinfunction "6_6") (pintype "passive"))
      (node (ref "BT1") (pin "2") (pinfunction "-_2") (pintype "passive"))
      (node (ref "C1") (pin "1") (pinfunction "1_1") (pintype "passive"))
      (node (ref "C10") (pin "1") (pinfunction "1_1") (pintype "passive"))
      (node (ref "C11") (pin "1") (pinfunction "1_1") (pintype "passive"))
      (node (ref "C12") (pin "1") (pinfunction "1_1") (pintype "passive"))
      (node (ref "C13") (pin "1") (pinfunction "1_1") (pintype "passive"))
      (node (ref "C14") (pin "1") (pinfunction "1_1") (pintype "passive"))
      (node (ref "C15") (pin "2") (pintype "passive"))
      (node (ref "C16") (pin "1") (pinfunction "1_1") (pintype "passive"))
      (node (ref "C17") (pin "1") (pinfunction "1_1") (pintype "passive"))
      (node (ref "C18") (pin "2") (pintype "passive"))
      (node (ref "C19") (pin "1") (pinfunction "1_1") (pintype "passive"))
      (node (ref "C2") (pin "1") (pinfunction "1_1") (pintype "passive"))
      (node (ref "C20") (pin "1") (pinfunction "1_1") (pintype "passive"))
      (node (ref "C21") (pin "1") (pinfunction "1_1") (pintype "passive"))
      (node (ref "C22") (pin "1") (pinfunction "1_1") (pintype "passive"))
      (node (ref "C23") (pin "1") (pinfunction "1_1") (pintype "passive"))
      (node (ref "C24") (pin "1") (pinfunction "1_1") (pintype "passive"))
      (node (ref "C25") (pin "1") (pinfunction "1_1") (pintype "passive"))
      (node (ref "C26") (pin "1") (pinfunction "1_1") (pintype "passive"))
      (node (ref "C27") (pin "1") (pinfunction "1_1") (pintype "passive"))
      (node (ref "C28") (pin "1") (pinfunction "1_1") (pintype "passive"))
      (node (ref "C29") (pin "1") (pinfunction "1_1") (pintype "passive"))
      (node (ref "C3") (pin "2") (pinfunction "2_2") (pintype "passive"))
      (node (ref "C30") (pin "1") (pinfunction "1_1") (pintype "passive"))
      (node (ref "C4") (pin "2") (pinfunction "2_2") (pintype "passive"))
      (node (ref "C5") (pin "2") (pinfunction "2_2") (pintype "passive"))
      (node (ref "C6") (pin "2") (pintype "passive"))
      (node (ref "C7") (pin "1") (pinfunction "1_1") (pintype "passive"))
      (node (ref "C8") (pin "1") (pinfunction "1_1") (pintype "passive"))
      (node (ref "C9") (pin "1") (pinfunction "1_1") (pintype "passive"))
      (node (ref "JTAG") (pin "10") (pinfunction "10_10") (pintype "passive"))
      (node (ref "JTAG") (pin "12") (pinfunction "12_12") (pintype "passive"))
      (node (ref "JTAG") (pin "14") (pinfunction "14_14") (pintype "passive"))
      (node (ref "JTAG") (pin "16") (pinfunction "16_16") (pintype "passive"))
      (node (ref "JTAG") (pin "18") (pinfunction "18_18") (pintype "passive"))
      (node (ref "JTAG") (pin "20") (pinfunction "20_20") (pintype "passive"))
      (node (ref "JTAG") (pin "4") (pinfunction "4_4") (pintype "passive"))
      (node (ref "JTAG") (pin "6") (pinfunction "6_6") (pintype "passive"))
      (node (ref "JTAG") (pin "8") (pinfunction "8_8") (pintype "passive"))
      (node (ref "R18") (pin "1") (pinfunction "1_1") (pintype "passive"))
      (node (ref "RESET") (pin "2") (pinfunction "2_2") (pintype "passive"))
      (node (ref "TFT 2.8'") (pin "22") (pinfunction "22_22") (pintype "passive"))
      (node (ref "TFT 2.8'") (pin "26") (pinfunction "26_26") (pintype "passive"))
      (node (ref "TFT 2.8'") (pin "27") (pinfunction "27_27") (pintype "passive"))
      (node (ref "U1") (pin "107") (pinfunction "VSS_107") (pintype "passive"))
      (node (ref "U1") (pin "120") (pinfunction "VSS_120") (pintype "passive"))
      (node (ref "U1") (pin "130") (pinfunction "VSS_130") (pintype "passive"))
      (node (ref "U1") (pin "143") (pinfunction "VSS_143") (pintype "passive"))
      (node (ref "U1") (pin "16") (pinfunction "VSS_16") (pintype "passive"))
      (node (ref "U1") (pin "30") (pinfunction "VSSA_30") (pintype "passive"))
      (node (ref "U1") (pin "38") (pinfunction "VSS_38") (pintype "passive"))
      (node (ref "U1") (pin "51") (pinfunction "VSS_51") (pintype "passive"))
      (node (ref "U1") (pin "61") (pinfunction "VSS_61") (pintype "passive"))
      (node (ref "U1") (pin "71") (pinfunction "VSS_71") (pintype "passive"))
      (node (ref "U1") (pin "83") (pinfunction "VSS_83") (pintype "passive"))
      (node (ref "U1") (pin "94") (pinfunction "VSS_94") (pintype "passive"))
      (node (ref "U2") (pin "1") (pinfunction "GND_1") (pintype "passive"))
      (node (ref "USB") (pin "5") (pinfunction "GND_5") (pintype "passive"))
      (node (ref "USB232") (pin "5") (pinfunction "GND_5") (pintype "passive"))
      (node (ref "VREF HEADER") (pin "4") (pinfunction "4_4") (pintype "passive"))
    )
    (net (code "121") (name "Net-(BOOT HEADER-Pad3)") (class "Default")
      (node (ref "BOOT HEADER") (pin "3") (pinfunction "3_3") (pintype "passive"))
      (node (ref "R12") (pin "2") (pinfunction "2_2") (pintype "passive"))
    )
    (net (code "122") (name "Net-(BOOT HEADER-Pad4)") (class "Default")
      (node (ref "BOOT HEADER") (pin "4") (pinfunction "4_4") (pintype "passive"))
      (node (ref "R13") (pin "1") (pinfunction "1_1") (pintype "passive"))
    )
    (net (code "123") (name "Net-(BT1-+)") (class "Default")
      (node (ref "BT1") (pin "1") (pinfunction "+_1") (pintype "passive"))
      (node (ref "D3") (pin "1") (pinfunction "1_1") (pintype "passive"))
    )
    (net (code "124") (name "Net-(CRY1-P1)") (class "Default")
      (node (ref "C4") (pin "1") (pinfunction "1_1") (pintype "passive"))
      (node (ref "CRY1") (pin "1") (pinfunction "P1_1") (pintype "passive"))
      (node (ref "U2") (pin "8") (pinfunction "XO_8") (pintype "passive"))
    )
    (net (code "125") (name "Net-(CRY1-P2)") (class "Default")
      (node (ref "C5") (pin "1") (pinfunction "1_1") (pintype "passive"))
      (node (ref "CRY1") (pin "2") (pinfunction "P2_2") (pintype "passive"))
      (node (ref "U2") (pin "7") (pinfunction "XI_7") (pintype "passive"))
    )
    (net (code "126") (name "Net-(CRY2-P1)") (class "Default")
      (node (ref "C9") (pin "2") (pinfunction "2_2") (pintype "passive"))
      (node (ref "CRY2") (pin "1") (pinfunction "P1_1") (pintype "passive"))
      (node (ref "U1") (pin "8") (pinfunction "PC14-OSC32_IN_8") (pintype "passive"))
    )
    (net (code "127") (name "Net-(CRY2-P2)") (class "Default")
      (node (ref "C10") (pin "2") (pinfunction "2_2") (pintype "passive"))
      (node (ref "CRY2") (pin "2") (pinfunction "P2_2") (pintype "passive"))
      (node (ref "U1") (pin "9") (pinfunction "PC15-OSC32_OUT_9") (pintype "passive"))
    )
    (net (code "128") (name "Net-(CRY3-P1)") (class "Default")
      (node (ref "C11") (pin "2") (pinfunction "2_2") (pintype "passive"))
      (node (ref "CRY3") (pin "1") (pinfunction "P1_1") (pintype "passive"))
      (node (ref "R9") (pin "2") (pinfunction "2_2") (pintype "passive"))
      (node (ref "U1") (pin "23") (pinfunction "OSC_IN_23") (pintype "passive"))
    )
    (net (code "129") (name "Net-(CRY3-P2)") (class "Default")
      (node (ref "C14") (pin "2") (pinfunction "2_2") (pintype "passive"))
      (node (ref "CRY3") (pin "2") (pinfunction "P2_2") (pintype "passive"))
      (node (ref "R9") (pin "1") (pinfunction "1_1") (pintype "passive"))
      (node (ref "U1") (pin "24") (pinfunction "OSC_OUT_24") (pintype "passive"))
    )
    (net (code "130") (name "Net-(J1-Pad1)") (class "Default")
      (node (ref "J1") (pin "1") (pinfunction "1_1") (pintype "passive"))
      (node (ref "R10") (pin "2") (pinfunction "2_2") (pintype "passive"))
    )
    (net (code "131") (name "Net-(R5-Pad2)") (class "Default")
      (node (ref "R5") (pin "2") (pinfunction "2_2") (pintype "passive"))
      (node (ref "USB HEADER") (pin "4") (pinfunction "4_4") (pintype "passive"))
    )
    (net (code "132") (name "Net-(R6-Pad2)") (class "Default")
      (node (ref "R6") (pin "2") (pinfunction "2_2") (pintype "passive"))
      (node (ref "R7") (pin "2") (pinfunction "2_2") (pintype "passive"))
      (node (ref "USB HEADER") (pin "3") (pinfunction "3_3") (pintype "passive"))
    )
    (net (code "133") (name "Net-(T1-B)") (class "Default")
      (node (ref "R2") (pin "2") (pinfunction "2_2") (pintype "passive"))
      (node (ref "T1") (pin "2") (pinfunction "B_2") (pintype "passive"))
    )
    (net (code "134") (name "Net-(T1-C)") (class "Default")
      (node (ref "D1") (pin "2") (pinfunction "2_2") (pintype "passive"))
      (node (ref "R1") (pin "2") (pinfunction "2_2") (pintype "passive"))
      (node (ref "T1") (pin "3") (pinfunction "C_3") (pintype "passive"))
    )
    (net (code "135") (name "Net-(T1-E)") (class "Default")
      (node (ref "R3") (pin "1") (pinfunction "1_1") (pintype "passive"))
      (node (ref "T1") (pin "1") (pinfunction "E_1") (pintype "passive"))
      (node (ref "U2") (pin "14") (pinfunction "RTS#_14") (pintype "passive"))
    )
    (net (code "136") (name "Net-(U1-VBAT)") (class "Default")
      (node (ref "C12") (pin "2") (pinfunction "2_2") (pintype "passive"))
      (node (ref "D2") (pin "2") (pinfunction "2_2") (pintype "passive"))
      (node (ref "D3") (pin "2") (pinfunction "2_2") (pintype "passive"))
      (node (ref "U1") (pin "6") (pinfunction "VBAT_6") (pintype "passive"))
    )
    (net (code "137") (name "Net-(U2-DTR#)") (class "Default")
      (node (ref "R2") (pin "1") (pinfunction "1_1") (pintype "passive"))
      (node (ref "U2") (pin "13") (pinfunction "DTR#_13") (pintype "passive"))
    )
    (net (code "138") (name "Net-(U2-V3)") (class "Default")
      (node (ref "C3") (pin "1") (pinfunction "1_1") (pintype "passive"))
      (node (ref "U2") (pin "4") (pinfunction "V3_4") (pintype "passive"))
    )
    (net (code "139") (name "Net-(USB-D+)") (class "Default")
      (node (ref "R7") (pin "1") (pinfunction "1_1") (pintype "passive"))
      (node (ref "USB") (pin "3") (pinfunction "D+_3") (pintype "passive"))
    )
    (net (code "140") (name "Net-(USB-D-)") (class "Default")
      (node (ref "R5") (pin "1") (pinfunction "1_1") (pintype "passive"))
      (node (ref "USB") (pin "2") (pinfunction "D-_2") (pintype "passive"))
    )
    (net (code "141") (name "Net-(V1-B)") (class "Default")
      (node (ref "R3") (pin "2") (pinfunction "2_2") (pintype "passive"))
      (node (ref "V1") (pin "2") (pinfunction "B_2") (pintype "passive"))
    )
    (net (code "142") (name "Net-(V1-C)") (class "Default")
      (node (ref "R4") (pin "2") (pinfunction "2_2") (pintype "passive"))
      (node (ref "V1") (pin "3") (pinfunction "C_3") (pintype "passive"))
    )
    (net (code "143") (name "VCC3.3") (class "Default")
      (node (ref "AMS1117") (pin "2") (pinfunction "Vout_2") (pintype "passive"))
      (node (ref "BOOT HEADER") (pin "1") (pinfunction "1_1") (pintype "passive"))
      (node (ref "BOOT HEADER") (pin "2") (pinfunction "2_2") (pintype "passive"))
      (node (ref "C15") (pin "1") (pintype "passive"))
      (node (ref "C17") (pin "2") (pinfunction "2_2") (pintype "passive"))
      (node (ref "C20") (pin "2") (pinfunction "2_2") (pintype "passive"))
      (node (ref "C21") (pin "2") (pinfunction "2_2") (pintype "passive"))
      (node (ref "C22") (pin "2") (pinfunction "2_2") (pintype "passive"))
      (node (ref "C23") (pin "2") (pinfunction "2_2") (pintype "passive"))
      (node (ref "C24") (pin "2") (pinfunction "2_2") (pintype "passive"))
      (node (ref "C25") (pin "2") (pinfunction "2_2") (pintype "passive"))
      (node (ref "C26") (pin "2") (pinfunction "2_2") (pintype "passive"))
      (node (ref "C27") (pin "2") (pinfunction "2_2") (pintype "passive"))
      (node (ref "C28") (pin "2") (pinfunction "2_2") (pintype "passive"))
      (node (ref "C29") (pin "2") (pinfunction "2_2") (pintype "passive"))
      (node (ref "C30") (pin "2") (pinfunction "2_2") (pintype "passive"))
      (node (ref "C7") (pin "2") (pinfunction "2_2") (pintype "passive"))
      (node (ref "D2") (pin "1") (pinfunction "1_1") (pintype "passive"))
      (node (ref "JTAG") (pin "1") (pinfunction "1_1") (pintype "passive"))
      (node (ref "JTAG") (pin "2") (pinfunction "2_2") (pintype "passive"))
      (node (ref "R1") (pin "1") (pinfunction "1_1") (pintype "passive"))
      (node (ref "R11") (pin "2") (pinfunction "2_2") (pintype "passive"))
      (node (ref "R14") (pin "2") (pinfunction "2_2") (pintype "passive"))
      (node (ref "R15") (pin "2") (pinfunction "2_2") (pintype "passive"))
      (node (ref "R16") (pin "2") (pinfunction "2_2") (pintype "passive"))
      (node (ref "R17") (pin "2") (pinfunction "2_2") (pintype "passive"))
      (node (ref "R6") (pin "1") (pinfunction "1_1") (pintype "passive"))
      (node (ref "R8") (pin "2") (pinfunction "2_2") (pintype "passive"))
      (node (ref "TFT 2.8'") (pin "24") (pinfunction "24_24") (pintype "passive"))
      (node (ref "TFT 2.8'") (pin "25") (pinfunction "25_25") (pintype "passive"))
      (node (ref "U1") (pin "108") (pinfunction "VDD_108") (pintype "passive"))
      (node (ref "U1") (pin "121") (pinfunction "VDD_121") (pintype "passive"))
      (node (ref "U1") (pin "131") (pinfunction "VDD_131") (pintype "passive"))
      (node (ref "U1") (pin "144") (pinfunction "VDD_144") (pintype "passive"))
      (node (ref "U1") (pin "17") (pinfunction "VDD_17") (pintype "passive"))
      (node (ref "U1") (pin "39") (pinfunction "VDD_39") (pintype "passive"))
      (node (ref "U1") (pin "52") (pinfunction "VDD_52") (pintype "passive"))
      (node (ref "U1") (pin "62") (pinfunction "VDD_62") (pintype "passive"))
      (node (ref "U1") (pin "72") (pinfunction "VDD_72") (pintype "passive"))
      (node (ref "U1") (pin "84") (pinfunction "VDD_84") (pintype "passive"))
      (node (ref "U1") (pin "95") (pinfunction "VDD_95") (pintype "passive"))
      (node (ref "V1") (pin "1") (pinfunction "E_1") (pintype "passive"))
    )
    (net (code "144") (name "VCC5") (class "Default")
      (node (ref "AMS1117") (pin "3") (pinfunction "Vin_3") (pintype "passive"))
      (node (ref "C1") (pin "2") (pinfunction "2_2") (pintype "passive"))
      (node (ref "C16") (pin "2") (pinfunction "2_2") (pintype "passive"))
      (node (ref "C2") (pin "2") (pinfunction "2_2") (pintype "passive"))
      (node (ref "C6") (pin "1") (pintype "passive"))
      (node (ref "C8") (pin "2") (pinfunction "2_2") (pintype "passive"))
      (node (ref "R10") (pin "1") (pinfunction "1_1") (pintype "passive"))
      (node (ref "TFT 2.8'") (pin "28") (pinfunction "28_28") (pintype "passive"))
      (node (ref "U2") (pin "16") (pinfunction "VCC_16") (pintype "passive"))
    )
    (net (code "145") (name "VDDA") (class "Default")
      (node (ref "C18") (pin "1") (pintype "passive"))
      (node (ref "C19") (pin "2") (pinfunction "2_2") (pintype "passive"))
      (node (ref "R11") (pin "1") (pinfunction "1_1") (pintype "passive"))
      (node (ref "U1") (pin "33") (pinfunction "VDDA_33") (pintype "passive"))
      (node (ref "VREF HEADER") (pin "2") (pinfunction "2_2") (pintype "passive"))
    )
    (net (code "146") (name "unconnected-(JTAG-Pad11)") (class "Default")
      (node (ref "JTAG") (pin "11") (pinfunction "11_11") (pintype "passive"))
    )
    (net (code "147") (name "unconnected-(JTAG-Pad17)") (class "Default")
      (node (ref "JTAG") (pin "17") (pinfunction "17_17") (pintype "passive"))
    )
    (net (code "148") (name "unconnected-(JTAG-Pad19)") (class "Default")
      (node (ref "JTAG") (pin "19") (pinfunction "19_19") (pintype "passive"))
    )
    (net (code "149") (name "unconnected-(TFT 2.8'-Pad32)") (class "Default")
      (node (ref "TFT 2.8'") (pin "32") (pinfunction "32_32") (pintype "passive"))
    )
    (net (code "150") (name "unconnected-(U1-NC-Pad106)") (class "Default")
      (node (ref "U1") (pin "106") (pinfunction "NC_106") (pintype "passive"))
    )
    (net (code "151") (name "unconnected-(U2-CTS#-Pad9)") (class "Default")
      (node (ref "U2") (pin "9") (pinfunction "CTS#_9") (pintype "passive"))
    )
    (net (code "152") (name "unconnected-(U2-DCD#-Pad12)") (class "Default")
      (node (ref "U2") (pin "12") (pinfunction "DCD#_12") (pintype "passive"))
    )
    (net (code "153") (name "unconnected-(U2-DSR#-Pad10)") (class "Default")
      (node (ref "U2") (pin "10") (pinfunction "DSR#_10") (pintype "passive"))
    )
    (net (code "154") (name "unconnected-(U2-R1#-Pad11)") (class "Default")
      (node (ref "U2") (pin "11") (pinfunction "R1#_11") (pintype "passive"))
    )
    (net (code "155") (name "unconnected-(U2-R232-Pad15)") (class "Default")
      (node (ref "U2") (pin "15") (pinfunction "R232_15") (pintype "passive"))
    )
    (net (code "156") (name "unconnected-(USB-ID-Pad4)") (class "Default")
      (node (ref "USB") (pin "4") (pinfunction "ID_4") (pintype "passive"))
    )
    (net (code "157") (name "unconnected-(USB-Pad0)") (class "Default")
      (node (ref "USB") (pin "0") (pinfunction "0_0") (pintype "passive"))
    )
    (net (code "158") (name "unconnected-(USB-Pad0)_1") (class "Default")
      (node (ref "USB") (pin "0") (pinfunction "0_0") (pintype "passive"))
    )
    (net (code "159") (name "unconnected-(USB-Pad0)_2") (class "Default")
      (node (ref "USB") (pin "0") (pinfunction "0_0") (pintype "passive"))
    )
    (net (code "160") (name "unconnected-(USB-Pad0)_3") (class "Default")
      (node (ref "USB") (pin "0") (pinfunction "0_0") (pintype "passive"))
    )
    (net (code "161") (name "unconnected-(USB232-ID-Pad4)") (class "Default")
      (node (ref "USB232") (pin "4") (pinfunction "ID_4") (pintype "passive"))
    )
    (net (code "162") (name "unconnected-(USB232-Pad0)") (class "Default")
      (node (ref "USB232") (pin "0") (pinfunction "0_0") (pintype "passive"))
    )
    (net (code "163") (name "unconnected-(USB232-Pad0)_1") (class "Default")
      (node (ref "USB232") (pin "0") (pinfunction "0_0") (pintype "passive"))
    )
    (net (code "164") (name "unconnected-(USB232-Pad0)_2") (class "Default")
      (node (ref "USB232") (pin "0") (pinfunction "0_0") (pintype "passive"))
    )
    (net (code "165") (name "unconnected-(USB232-Pad0)_3") (class "Default")
      (node (ref "USB232") (pin "0") (pinfunction "0_0") (pintype "passive"))
    )
  )
)
